# ECG_7_by_7.net
KiCad netlist of a schematic drawn in EAGLE
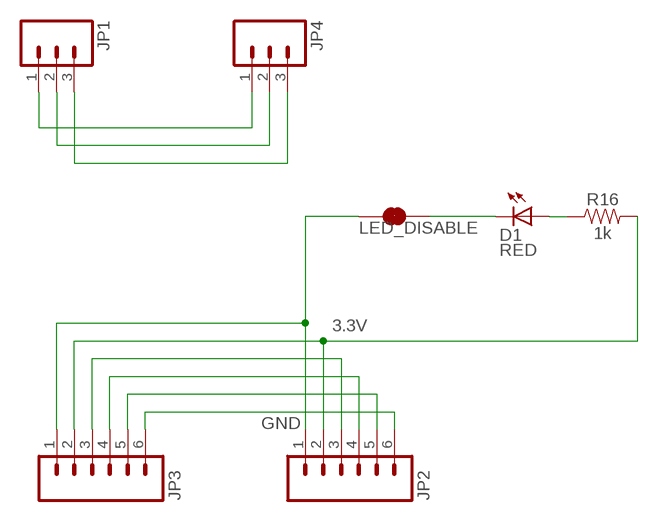
[diagram p0: schematic, sheet 1]

(export (version "E")
  (design (tool "Eeschema 10.0.6"))
  (components
    (comp (ref "D1")
      (value "RED")
      (footprint "eagle-import:LED-0603")
      (libsource (lib "eagle-import") (part "LED-RED0603"))
    )
    (comp (ref "JP1")
      (value "M03PTH")
      (footprint "eagle-import:1X03")
      (libsource (lib "eagle-import") (part "M03PTH"))
    )
    (comp (ref "JP2")
      (value "M06SIP")
      (footprint "eagle-import:1X06")
      (libsource (lib "eagle-import") (part "M06SIP"))
    )
    (comp (ref "JP3")
      (value "M06SIP")
      (footprint "eagle-import:1X06")
      (libsource (lib "eagle-import") (part "M06SIP"))
    )
    (comp (ref "JP4")
      (value "M03PTH")
      (footprint "eagle-import:1X03")
      (libsource (lib "eagle-import") (part "M03PTH"))
    )
    (comp (ref "LED_DISABLE")
      (value "JUMPER-SMT_2_NC_TRACE_SILK")
      (footprint "eagle-import:SMT-JUMPER_2_NC_TRACE_SILK")
      (libsource (lib "eagle-import") (part "JUMPER-SMT_2_NC_TRACE_SILK"))
    )
    (comp (ref "R16")
      (value "1k")
      (footprint "eagle-import:0603")
      (libsource (lib "eagle-import") (part "1KOHM-0603-1/10W-1%"))
    )
  )
  (nets
    (net (code "1") (name "/3.3V") (class "Default")
      (node (ref "JP2") (pin "2") (pinfunction "2_2") (pintype "passive"))
      (node (ref "JP3") (pin "2") (pinfunction "2_2") (pintype "passive"))
      (node (ref "R16") (pin "2") (pinfunction "2_2") (pintype "passive"))
    )
    (net (code "2") (name "/GND") (class "Default")
      (node (ref "JP2") (pin "1") (pinfunction "1_1") (pintype "passive"))
      (node (ref "JP3") (pin "1") (pinfunction "1_1") (pintype "passive"))
      (node (ref "LED_DISABLE") (pin "1") (pinfunction "1_1") (pintype "passive"))
    )
    (net (code "3") (name "Net-(D1-PadA)") (class "Default")
      (node (ref "D1") (pin "A") (pinfunction "A_A") (pintype "passive"))
      (node (ref "R16") (pin "1") (pinfunction "1_1") (pintype "passive"))
    )
    (net (code "4") (name "Net-(D1-PadC)") (class "Default")
      (node (ref "D1") (pin "C") (pinfunction "C_C") (pintype "passive"))
      (node (ref "LED_DISABLE") (pin "2") (pinfunction "2_2") (pintype "passive"))
    )
    (net (code "5") (name "Net-(JP1-Pad1)") (class "Default")
      (node (ref "JP1") (pin "1") (pinfunction "1_1") (pintype "passive"))
      (node (ref "JP4") (pin "1") (pinfunction "1_1") (pintype "passive"))
    )
    (net (code "6") (name "Net-(JP1-Pad2)") (class "Default")
      (node (ref "JP1") (pin "2") (pinfunction "2_2") (pintype "passive"))
      (node (ref "JP4") (pin "2") (pinfunction "2_2") (pintype "passive"))
    )
    (net (code "7") (name "Net-(JP1-Pad3)") (class "Default")
      (node (ref "JP1") (pin "3") (pinfunction "3_3") (pintype "passive"))
      (node (ref "JP4") (pin "3") (pinfunction "3_3") (pintype "passive"))
    )
    (net (code "8") (name "Net-(JP2-Pad3)") (class "Default")
      (node (ref "JP2") (pin "3") (pinfunction "3_3") (pintype "passive"))
      (node (ref "JP3") (pin "3") (pinfunction "3_3") (pintype "passive"))
    )
    (net (code "9") (name "Net-(JP2-Pad4)") (class "Default")
      (node (ref "JP2") (pin "4") (pinfunction "4_4") (pintype "passive"))
      (node (ref "JP3") (pin "4") (pinfunction "4_4") (pintype "passive"))
    )
    (net (code "10") (name "Net-(JP2-Pad5)") (class "Default")
      (node (ref "JP2") (pin "5") (pinfunction "5_5") (pintype "passive"))
      (node (ref "JP3") (pin "5") (pinfunction "5_5") (pintype "passive"))
    )
    (net (code "11") (name "Net-(JP2-Pad6)") (class "Default")
      (node (ref "JP2") (pin "6") (pinfunction "6_6") (pintype "passive"))
      (node (ref "JP3") (pin "6") (pinfunction "6_6") (pintype "passive"))
    )
  )
)
